# Linear_PowerSupply.net
KiCad netlist of a schematic drawn in EAGLE
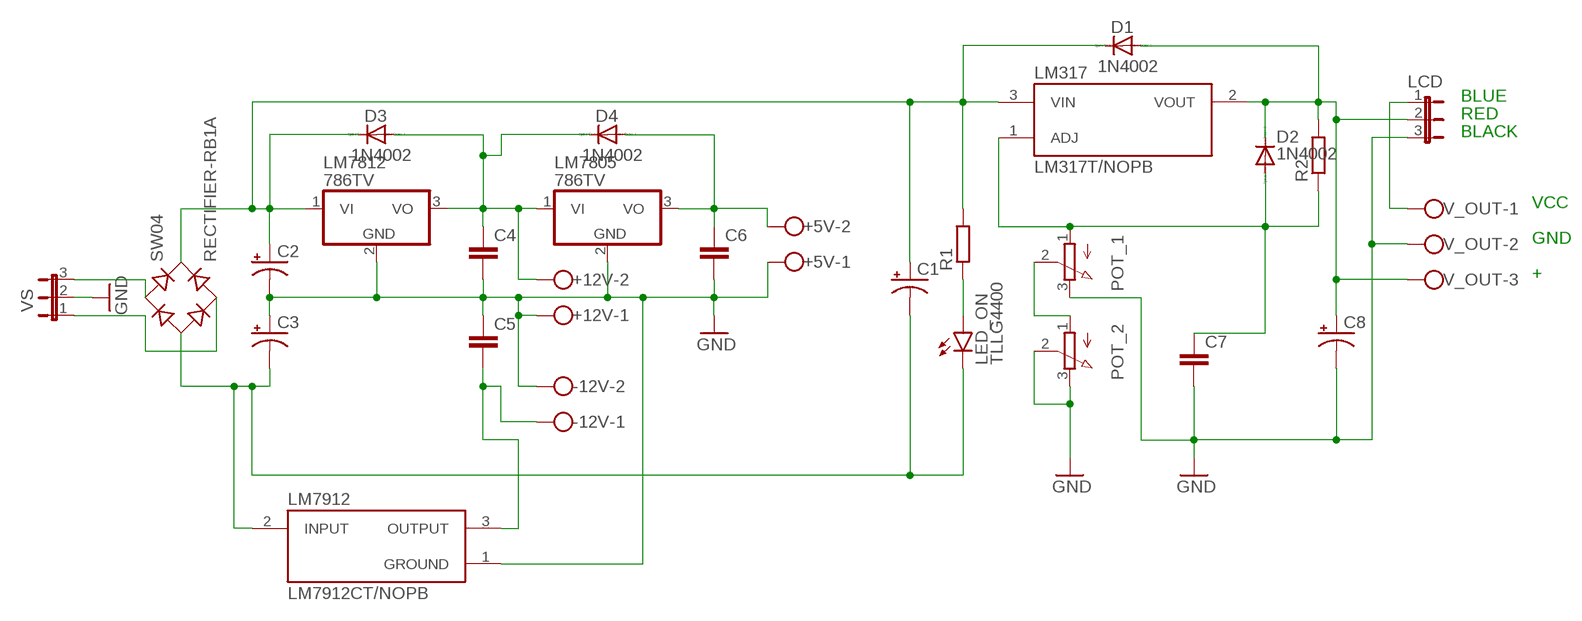
[diagram p0: schematic, sheet 1]

(export (version "E")
  (design (tool "Eeschema 10.0.6"))
  (components
    (comp (ref "+5V")
      (value "W237-102")
      (footprint "eagle-import:W237-102")
      (fields (field (name "MPN") "237-102"))
      (libsource (lib "eagle-import") (part "W237-102"))
    )
    (comp (ref "+12V")
      (value "W237-102")
      (footprint "eagle-import:W237-102")
      (fields (field (name "MPN") "237-102"))
      (libsource (lib "eagle-import") (part "W237-102"))
    )
    (comp (ref "-12V")
      (value "W237-102")
      (footprint "eagle-import:W237-102")
      (fields (field (name "MPN") "237-102"))
      (libsource (lib "eagle-import") (part "W237-102"))
    )
    (comp (ref "C1")
      (value "CPOL-USE5-13")
      (footprint "eagle-import:E5-13")
      (libsource (lib "eagle-import") (part "CPOL-USE5-13"))
    )
    (comp (ref "C2")
      (value "CPOL-USE3.5-8")
      (footprint "eagle-import:E3,5-8")
      (libsource (lib "eagle-import") (part "CPOL-USE3.5-8"))
    )
    (comp (ref "C3")
      (value "CPOL-USE3.5-8")
      (footprint "eagle-import:E3,5-8")
      (libsource (lib "eagle-import") (part "CPOL-USE3.5-8"))
    )
    (comp (ref "C4")
      (value "C-EU025-024X044")
      (footprint "eagle-import:C025-024X044")
      (libsource (lib "eagle-import") (part "C-EU025-024X044"))
    )
    (comp (ref "C5")
      (value "C-EU025-024X044")
      (footprint "eagle-import:C025-024X044")
      (libsource (lib "eagle-import") (part "C-EU025-024X044"))
    )
    (comp (ref "C6")
      (value "C-EU025-024X044")
      (footprint "eagle-import:C025-024X044")
      (libsource (lib "eagle-import") (part "C-EU025-024X044"))
    )
    (comp (ref "C7")
      (value "C-EU025-024X044")
      (footprint "eagle-import:C025-024X044")
      (libsource (lib "eagle-import") (part "C-EU025-024X044"))
    )
    (comp (ref "C8")
      (value "CPOL-USE3.5-8")
      (footprint "eagle-import:E3,5-8")
      (libsource (lib "eagle-import") (part "CPOL-USE3.5-8"))
    )
    (comp (ref "D1")
      (value "1N4002")
      (footprint "eagle-import:DO41-10")
      (libsource (lib "eagle-import") (part "1N4004"))
    )
    (comp (ref "D2")
      (value "1N4002")
      (footprint "eagle-import:DO41-10")
      (libsource (lib "eagle-import") (part "1N4004"))
    )
    (comp (ref "D3")
      (value "1N4002")
      (footprint "eagle-import:DO41-10")
      (libsource (lib "eagle-import") (part "1N4004"))
    )
    (comp (ref "D4")
      (value "1N4002")
      (footprint "eagle-import:DO41-10")
      (libsource (lib "eagle-import") (part "1N4004"))
    )
    (comp (ref "LCD")
      (value "JP2E")
      (footprint "eagle-import:JP2")
      (libsource (lib "eagle-import") (part "JP2E"))
    )
    (comp (ref "LED_ON")
      (value "TLLG4400")
      (footprint "eagle-import:LED3MM")
      (fields (field (name "MF") "VISHAY SEMICONDUCTOR"))
      (libsource (lib "eagle-import") (part "TLLG4400"))
    )
    (comp (ref "LM317")
      (value "LM317T/NOPB")
      (footprint "eagle-import:LM317T_NOPB_TO254P1054X470X1955-3")
      (fields (field (name "MANUFACTURER") "Texas Instruments"))
      (libsource (lib "eagle-import") (part "LM317T/NOPB"))
    )
    (comp (ref "LM7805")
      (value "786TV")
      (footprint "eagle-import:TO220V")
      (libsource (lib "eagle-import") (part "78TV6"))
    )
    (comp (ref "LM7812")
      (value "786TV")
      (footprint "eagle-import:TO220V")
      (libsource (lib "eagle-import") (part "78TV6"))
    )
    (comp (ref "LM7912")
      (value "LM7912CT/NOPB")
      (footprint "eagle-import:TO254P1054X470X1955-3")
      (fields (field (name "MANUFACTURER") "Texas Instruments"))
      (libsource (lib "eagle-import") (part "LM7912CT/NOPB"))
    )
    (comp (ref "POT_1")
      (value "3RP/1610N")
      (footprint "eagle-import:3RP_1610N")
      (libsource (lib "eagle-import") (part "3RP/1610N"))
    )
    (comp (ref "POT_2")
      (value "3RP/1610N")
      (footprint "eagle-import:3RP_1610N")
      (libsource (lib "eagle-import") (part "3RP/1610N"))
    )
    (comp (ref "R1")
      (value "R-EU_0207/10")
      (footprint "eagle-import:0207_10")
      (libsource (lib "eagle-import") (part "R-EU_0207/10"))
    )
    (comp (ref "R2")
      (value "R-EU_0207/10")
      (footprint "eagle-import:0207_10")
      (libsource (lib "eagle-import") (part "R-EU_0207/10"))
    )
    (comp (ref "SW04")
      (value "RECTIFIER-RB1A")
      (footprint "eagle-import:RB1A")
      (libsource (lib "eagle-import") (part "RECTIFIER-RB1A"))
    )
    (comp (ref "VS")
      (value "JP2E")
      (footprint "eagle-import:JP2")
      (libsource (lib "eagle-import") (part "JP2E"))
    )
    (comp (ref "V_OUT")
      (value "W237-103")
      (footprint "eagle-import:W237-103")
      (fields (field (name "MPN") "237-103"))
      (libsource (lib "eagle-import") (part "W237-103"))
    )
  )
  (nets
    (net (code "1") (name "GND") (class "Default")
      (node (ref "+12V") (pin "1") (pinfunction "KL_1") (pintype "passive"))
      (node (ref "+5V") (pin "1") (pinfunction "KL_1") (pintype "passive"))
      (node (ref "-12V") (pin "2") (pinfunction "KL_2") (pintype "passive"))
      (node (ref "C2") (pin "-") (pinfunction "-_-") (pintype "passive"))
      (node (ref "C3") (pin "+") (pinfunction "+_+") (pintype "passive"))
      (node (ref "C4") (pin "2") (pinfunction "2_2") (pintype "passive"))
      (node (ref "C5") (pin "1") (pinfunction "1_1") (pintype "passive"))
      (node (ref "C6") (pin "2") (pinfunction "2_2") (pintype "passive"))
      (node (ref "C7") (pin "2") (pinfunction "2_2") (pintype "passive"))
      (node (ref "C8") (pin "-") (pinfunction "-_-") (pintype "passive"))
      (node (ref "LCD") (pin "3") (pinfunction "3_3") (pintype "passive"))
      (node (ref "LM7805") (pin "2") (pinfunction "GND_2") (pintype "passive"))
      (node (ref "LM7812") (pin "2") (pinfunction "GND_2") (pintype "passive"))
      (node (ref "LM7912") (pin "1") (pinfunction "GROUND_1") (pintype "power_in"))
      (node (ref "POT_1") (pin "3") (pinfunction "E_3") (pintype "passive"))
      (node (ref "POT_2") (pin "2") (pinfunction "S_2") (pintype "passive"))
      (node (ref "POT_2") (pin "3") (pinfunction "E_3") (pintype "passive"))
      (node (ref "VS") (pin "2") (pinfunction "2_2") (pintype "passive"))
      (node (ref "V_OUT") (pin "2") (pinfunction "KL_2") (pintype "passive"))
    )
    (net (code "2") (name "Net-(+5VB-KL)") (class "Default")
      (node (ref "+5V") (pin "2") (pinfunction "KL_2") (pintype "passive"))
      (node (ref "C6") (pin "1") (pinfunction "1_1") (pintype "passive"))
      (node (ref "D4") (pin "A") (pinfunction "A_A") (pintype "passive"))
      (node (ref "LM7805") (pin "3") (pinfunction "VO_3") (pintype "passive"))
    )
    (net (code "3") (name "Net-(+12VB-KL)") (class "Default")
      (node (ref "+12V") (pin "2") (pinfunction "KL_2") (pintype "passive"))
      (node (ref "C4") (pin "1") (pinfunction "1_1") (pintype "passive"))
      (node (ref "D3") (pin "A") (pinfunction "A_A") (pintype "passive"))
      (node (ref "D4") (pin "C") (pinfunction "C_C") (pintype "passive"))
      (node (ref "LM7805") (pin "1") (pinfunction "VI_1") (pintype "input"))
      (node (ref "LM7812") (pin "3") (pinfunction "VO_3") (pintype "passive"))
    )
    (net (code "4") (name "Net-(-12VA-KL)") (class "Default")
      (node (ref "-12V") (pin "1") (pinfunction "KL_1") (pintype "passive"))
      (node (ref "C5") (pin "2") (pinfunction "2_2") (pintype "passive"))
      (node (ref "LM7912") (pin "3") (pinfunction "OUTPUT_3") (pintype "output"))
    )
    (net (code "5") (name "Net-(LED_ON-C)") (class "Default")
      (node (ref "C1") (pin "-") (pinfunction "-_-") (pintype "passive"))
      (node (ref "C3") (pin "-") (pinfunction "-_-") (pintype "passive"))
      (node (ref "LED_ON") (pin "K") (pinfunction "C_K") (pintype "passive"))
      (node (ref "LM7912") (pin "2") (pinfunction "INPUT_2") (pintype "input"))
      (node (ref "SW04") (pin "-") (pinfunction "-_-") (pintype "passive"))
    )
    (net (code "6") (name "Net-(LED_ON-PadA)") (class "Default")
      (node (ref "LED_ON") (pin "A") (pinfunction "A_A") (pintype "passive"))
      (node (ref "R1") (pin "1") (pinfunction "1_1") (pintype "passive"))
    )
    (net (code "7") (name "Net-(LM317-ADJ)") (class "Default")
      (node (ref "C7") (pin "1") (pinfunction "1_1") (pintype "passive"))
      (node (ref "D2") (pin "A") (pinfunction "A_A") (pintype "passive"))
      (node (ref "LM317") (pin "1") (pinfunction "ADJ_1") (pintype "passive"))
      (node (ref "POT_1") (pin "1") (pinfunction "A_1") (pintype "passive"))
      (node (ref "R2") (pin "1") (pinfunction "1_1") (pintype "passive"))
    )
    (net (code "8") (name "Net-(LM317-VIN)") (class "Default")
      (node (ref "C1") (pin "+") (pinfunction "+_+") (pintype "passive"))
      (node (ref "C2") (pin "+") (pinfunction "+_+") (pintype "passive"))
      (node (ref "D1") (pin "C") (pinfunction "C_C") (pintype "passive"))
      (node (ref "D3") (pin "C") (pinfunction "C_C") (pintype "passive"))
      (node (ref "LM317") (pin "3") (pinfunction "VIN_3") (pintype "input"))
      (node (ref "LM7812") (pin "1") (pinfunction "VI_1") (pintype "input"))
      (node (ref "R1") (pin "2") (pinfunction "2_2") (pintype "passive"))
      (node (ref "SW04") (pin "+") (pinfunction "+_+") (pintype "passive"))
    )
    (net (code "9") (name "Net-(LM317-VOUT)") (class "Default")
      (node (ref "C8") (pin "+") (pinfunction "+_+") (pintype "passive"))
      (node (ref "D1") (pin "A") (pinfunction "A_A") (pintype "passive"))
      (node (ref "D2") (pin "C") (pinfunction "C_C") (pintype "passive"))
      (node (ref "LCD") (pin "2") (pinfunction "2_2") (pintype "passive"))
      (node (ref "LM317") (pin "2") (pinfunction "VOUT_2") (pintype "output"))
      (node (ref "R2") (pin "2") (pinfunction "2_2") (pintype "passive"))
      (node (ref "V_OUT") (pin "3") (pinfunction "KL_3") (pintype "passive"))
    )
    (net (code "10") (name "Net-(POT_1-S)") (class "Default")
      (node (ref "POT_1") (pin "2") (pinfunction "S_2") (pintype "passive"))
      (node (ref "POT_2") (pin "1") (pinfunction "A_1") (pintype "passive"))
    )
    (net (code "11") (name "Net-(SW04-PadAC1)") (class "Default")
      (node (ref "SW04") (pin "AC1") (pinfunction "AC1_AC1") (pintype "passive"))
      (node (ref "VS") (pin "3") (pinfunction "3_3") (pintype "passive"))
    )
    (net (code "12") (name "Net-(SW04-PadAC2)") (class "Default")
      (node (ref "SW04") (pin "AC2") (pinfunction "AC2_AC2") (pintype "passive"))
      (node (ref "VS") (pin "1") (pinfunction "1_1") (pintype "passive"))
    )
    (net (code "13") (name "Net-(V_OUTA-KL)") (class "Default")
      (node (ref "LCD") (pin "1") (pinfunction "1_1") (pintype "passive"))
      (node (ref "V_OUT") (pin "1") (pinfunction "KL_1") (pintype "passive"))
    )
  )
)
